# oled.net
KiCad netlist of a schematic drawn in Altium Designer
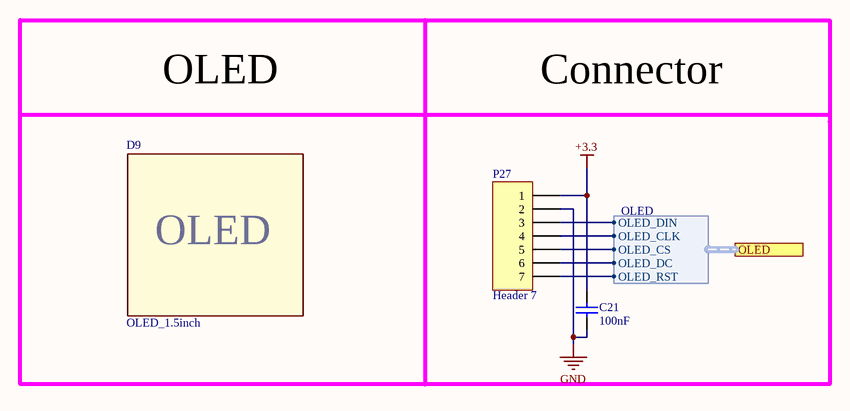
[diagram p0: oled.SchDoc]

(export (version "E")
  (design (tool "Eeschema 10.0.6"))
  (components
    (comp (ref "C21")
      (value "100nF")
      (footprint "CAP_0402i_1005m -N")
      (description "capacitor")
      (libsource (lib "IDSC std generic parts") (part "Cap"))
    )
    (comp (ref "D9")
      (value "OLED_1.5inch")
      (footprint "oled_1.5inch")
      (description "128x128 1.5inch RGB OLED Display Modul SPI")
      (libsource (lib "BMA_lib") (part "OLED_1.5inch"))
    )
    (comp (ref "P27")
      (value "Header 7")
      (footprint "HDR1X7")
      (description "Header, 7-Pin")
      (libsource (lib "IDSC std connectors") (part "Header 7"))
    )
  )
  (nets
    (net (code "2") (name "+3.3") (class "Default")
      (node (ref "C21") (pin "1") (pinfunction "1_1") (pintype "passive"))
      (node (ref "P27") (pin "1") (pinfunction "1_1") (pintype "passive"))
    )
    (net (code "3") (name "/OLED_CLK") (class "Default")
      (node (ref "P27") (pin "4") (pinfunction "4_4") (pintype "passive"))
    )
    (net (code "4") (name "/OLED_CS") (class "Default")
      (node (ref "P27") (pin "5") (pinfunction "5_5") (pintype "passive"))
    )
    (net (code "5") (name "/OLED_DC") (class "Default")
      (node (ref "P27") (pin "6") (pinfunction "6_6") (pintype "passive"))
    )
    (net (code "6") (name "/OLED_DIN") (class "Default")
      (node (ref "P27") (pin "3") (pinfunction "3_3") (pintype "passive"))
    )
    (net (code "7") (name "/OLED_RST") (class "Default")
      (node (ref "P27") (pin "7") (pinfunction "7_7") (pintype "passive"))
    )
    (net (code "9") (name "GND") (class "Default")
      (node (ref "C21") (pin "2") (pinfunction "2_2") (pintype "passive"))
      (node (ref "P27") (pin "2") (pinfunction "2_2") (pintype "passive"))
    )
  )
)
